# custom_hat_v_beta.net
KiCad netlist of a schematic drawn in EAGLE
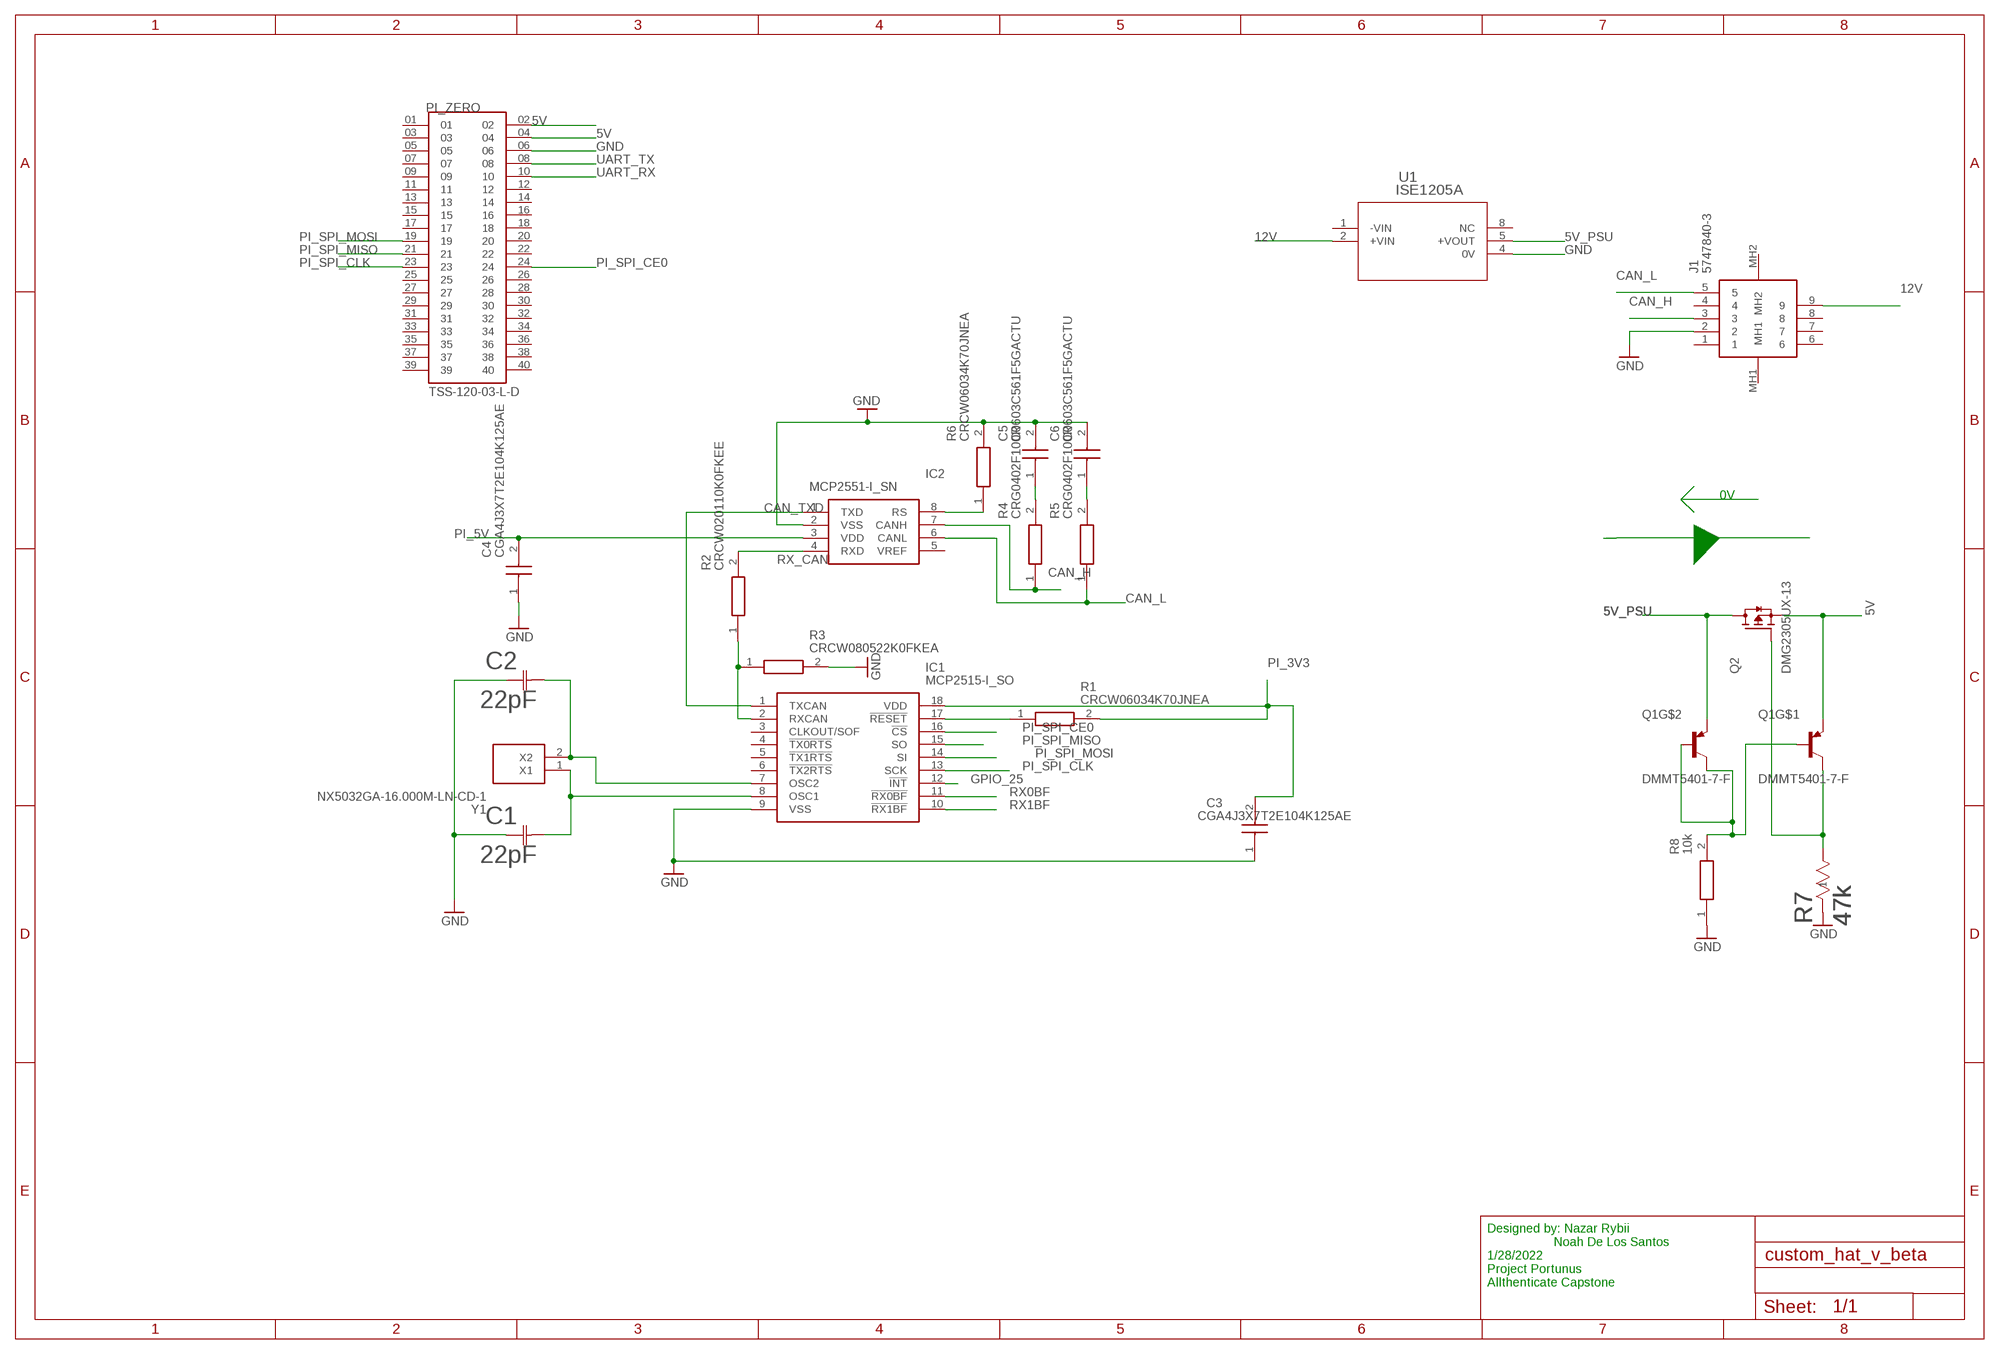
[diagram p0: schematic, sheet 1]

(export (version "E")
  (design (tool "Eeschema 10.0.6"))
  (components
    (comp (ref "C1")
      (value "22pF")
      (footprint "eagle-import:CAP_CL21_SAM")
      (fields
        (field (name "MANUFACTURER_PART_NUMBER") "CL21C220JBANNNC")
        (field (name "COPYRIGHT") "Copyright (C) 2022 Ultra Librarian. All rights reserved.")
      )
      (libsource (lib "eagle-import") (part "CL21C220JBANNNC"))
    )
    (comp (ref "C2")
      (value "22pF")
      (footprint "eagle-import:CAP_CL21_SAM")
      (fields
        (field (name "MANUFACTURER_PART_NUMBER") "CL21C220JBANNNC")
        (field (name "COPYRIGHT") "Copyright (C) 2022 Ultra Librarian. All rights reserved.")
      )
      (libsource (lib "eagle-import") (part "CL21C220JBANNNC"))
    )
    (comp (ref "C3")
      (value "CGA4J3X7T2E104K125AE")
      (footprint "eagle-import:CAPC2012X145N")
      (fields (field (name "MOUSER_PART_NUMBER") "810-CGA4J3X7T2E104KS"))
      (libsource (lib "eagle-import") (part "CGA4J3X7T2E104K125AE"))
    )
    (comp (ref "C4")
      (value "CGA4J3X7T2E104K125AE")
      (footprint "eagle-import:CAPC2012X145N")
      (fields (field (name "MOUSER_PART_NUMBER") "810-CGA4J3X7T2E104KS"))
      (libsource (lib "eagle-import") (part "CGA4J3X7T2E104K125AE"))
    )
    (comp (ref "C5")
      (value "C0603C561F5GACTU")
      (footprint "eagle-import:CAPC1608X87N")
      (fields (field (name "MOUSER_PART_NUMBER") "80-C0603C561F5G"))
      (libsource (lib "eagle-import") (part "C0603C561F5GACTU"))
    )
    (comp (ref "C6")
      (value "C0603C561F5GACTU")
      (footprint "eagle-import:CAPC1608X87N")
      (fields (field (name "MOUSER_PART_NUMBER") "80-C0603C561F5G"))
      (libsource (lib "eagle-import") (part "C0603C561F5GACTU"))
    )
    (comp (ref "IC1")
      (value "MCP2515-I_SO")
      (footprint "eagle-import:SOIC127P1030X265-18N")
      (fields
        (field (name "ARROW_PART_NUMBER") "MCP2515-I/SO")
        (field (name "MOUSER_PART_NUMBER") "579-MCP2515-I/SO")
      )
      (libsource (lib "eagle-import") (part "MCP2515-I_SO"))
    )
    (comp (ref "IC2")
      (value "MCP2551-I_SN")
      (footprint "eagle-import:SOIC127P600X175-8N")
      (fields
        (field (name "ARROW_PART_NUMBER") "MCP2551-I/SN")
        (field (name "MOUSER_PART_NUMBER") "579-MCP2551-I/SN")
      )
      (libsource (lib "eagle-import") (part "MCP2551-I_SN"))
    )
    (comp (ref "J1")
      (value "5747840-3")
      (footprint "eagle-import:57478403")
      (fields (field (name "MOUSER_PART_NUMBER") "571-5747840-3"))
      (libsource (lib "eagle-import") (part "5747840-3"))
    )
    (comp (ref "PI_ZERO")
      (value "TSS-120-03-L-D")
      (footprint "eagle-import:SAMTEC_TSS-120-03-L-D")
      (fields (field (name "MF") "Samtec"))
      (libsource (lib "eagle-import") (part "TSS-120-03-L-D"))
    )
    (comp (ref "Q1")
      (value "DMMT5401-7-F")
      (footprint "eagle-import:SOT95P285X140-6N")
      (fields (field (name "MF") "Diodes Inc."))
      (libsource (lib "eagle-import") (part "DMMT5401-7-F"))
    )
    (comp (ref "Q2")
      (value "DMG2305UX-13")
      (footprint "eagle-import:SOT91P240X110-3N")
      (fields (field (name "MF") "Diodes Inc."))
      (libsource (lib "eagle-import") (part "DMG2305UX-13"))
    )
    (comp (ref "R1")
      (value "CRCW06034K70JNEA")
      (footprint "eagle-import:RESC1608X50N")
      (fields (field (name "MOUSER_PART_NUMBER") "71-CRCW0603J-4.7K-E3"))
      (libsource (lib "eagle-import") (part "CRCW06034K70JNEA"))
    )
    (comp (ref "R2")
      (value "CRCW020110K0FKEE")
      (footprint "eagle-import:RESC0603X28N")
      (libsource (lib "eagle-import") (part "CRCW020110K0FKEE"))
    )
    (comp (ref "R3")
      (value "CRCW080522K0FKEA")
      (footprint "eagle-import:RESC2012X50N")
      (fields (field (name "MOUSER_PART_NUMBER") "71-CRCW0805-22K-E3"))
      (libsource (lib "eagle-import") (part "CRCW080522K0FKEA"))
    )
    (comp (ref "R4")
      (value "CRG0402F100R")
      (footprint "eagle-import:RESC1005X40N")
      (fields (field (name "MOUSER_PART_NUMBER") "279-CRG0402F100R"))
      (libsource (lib "eagle-import") (part "CRG0402F100R"))
    )
    (comp (ref "R5")
      (value "CRG0402F100R")
      (footprint "eagle-import:RESC1005X40N")
      (fields (field (name "MOUSER_PART_NUMBER") "279-CRG0402F100R"))
      (libsource (lib "eagle-import") (part "CRG0402F100R"))
    )
    (comp (ref "R6")
      (value "CRCW06034K70JNEA")
      (footprint "eagle-import:RESC1608X50N")
      (fields (field (name "MOUSER_PART_NUMBER") "71-CRCW0603J-4.7K-E3"))
      (libsource (lib "eagle-import") (part "CRCW06034K70JNEA"))
    )
    (comp (ref "R7")
      (value "47k")
      (footprint "eagle-import:RC0603N_YAG")
      (fields
        (field (name "MANUFACTURER_PART_NUMBER") "RC0603FR-0747KL")
        (field (name "COPYRIGHT") "Copyright (C) 2022 Ultra Librarian. All rights reserved.")
      )
      (libsource (lib "eagle-import") (part "RC0603FR-0747KL"))
    )
    (comp (ref "R8")
      (value "10k")
      (footprint "eagle-import:RESC2012X50N")
      (fields
        (field (name "ARROW_PART_NUMBER") "CRCW080510K0FKEC")
        (field (name "MOUSER_PART_NUMBER") "71-CRCW080510K0FKEC")
      )
      (libsource (lib "eagle-import") (part "CRCW080510K0FKEC"))
    )
    (comp (ref "U1")
      (value "ISE1205A")
      (footprint "eagle-import:ISE1205A_XPP")
      (fields (field (name "COPYRIGHT") "Copyright (C) 2022 Ultra Librarian. All rights reserved."))
      (libsource (lib "eagle-import") (part "ISE1205A"))
    )
    (comp (ref "Y1")
      (value "NX5032GA-16.000M-LN-CD-1")
      (footprint "eagle-import:NX5032GA16000000MHZLNCD1")
      (fields (field (name "MOUSER_PART_NUMBER") "344-NX5032GA16MLNCD1"))
      (libsource (lib "eagle-import") (part "NX5032GA-16.000M-LN-CD-1"))
    )
  )
  (nets
    (net (code "1") (name "/-VIN") (class "Default")
      (node (ref "U1") (pin "1") (pinfunction "-VIN_1") (pintype "power_in"))
    )
    (net (code "2") (name "/5V") (class "Default")
      (node (ref "PI_ZERO") (pin "02") (pinfunction "02_02") (pintype "passive"))
      (node (ref "PI_ZERO") (pin "04") (pinfunction "04_04") (pintype "passive"))
      (node (ref "Q1") (pin "6") (pinfunction "E_6") (pintype "passive"))
      (node (ref "Q2") (pin "2") (pinfunction "S_2") (pintype "passive"))
    )
    (net (code "3") (name "/5V_PSU") (class "Default")
      (node (ref "Q1") (pin "5") (pinfunction "E_5") (pintype "passive"))
      (node (ref "Q2") (pin "3") (pinfunction "D_3") (pintype "passive"))
      (node (ref "U1") (pin "5") (pinfunction "+VOUT_5") (pintype "output"))
    )
    (net (code "4") (name "/12V") (class "Default")
      (node (ref "J1") (pin "9") (pinfunction "9_9") (pintype "bidirectional"))
      (node (ref "U1") (pin "2") (pinfunction "+VIN_2") (pintype "power_in"))
    )
    (net (code "5") (name "/CAN_H") (class "Default")
      (node (ref "IC2") (pin "7") (pinfunction "CANH_7") (pintype "bidirectional"))
      (node (ref "J1") (pin "3") (pinfunction "3_3") (pintype "bidirectional"))
      (node (ref "R4") (pin "1") (pinfunction "1_1") (pintype "bidirectional"))
    )
    (net (code "6") (name "/CAN_L") (class "Default")
      (node (ref "IC2") (pin "6") (pinfunction "CANL_6") (pintype "bidirectional"))
      (node (ref "J1") (pin "5") (pinfunction "5_5") (pintype "bidirectional"))
      (node (ref "R5") (pin "1") (pinfunction "1_1") (pintype "bidirectional"))
    )
    (net (code "7") (name "/CAN_TXD") (class "Default")
      (node (ref "IC1") (pin "1") (pinfunction "TXCAN_1") (pintype "bidirectional"))
      (node (ref "IC2") (pin "1") (pinfunction "TXD_1") (pintype "bidirectional"))
    )
    (net (code "8") (name "/GPIO_25") (class "Default")
      (node (ref "IC1") (pin "12") (pinfunction "~{INT}_12") (pintype "bidirectional"))
    )
    (net (code "9") (name "/PI_3V3") (class "Default")
      (node (ref "C3") (pin "2") (pinfunction "2_2") (pintype "bidirectional"))
      (node (ref "IC1") (pin "18") (pinfunction "VDD_18") (pintype "bidirectional"))
      (node (ref "R1") (pin "2") (pinfunction "2_2") (pintype "bidirectional"))
    )
    (net (code "10") (name "/PI_5V") (class "Default")
      (node (ref "C4") (pin "2") (pinfunction "2_2") (pintype "bidirectional"))
      (node (ref "IC2") (pin "3") (pinfunction "VDD_3") (pintype "bidirectional"))
    )
    (net (code "11") (name "/PI_SPI_CE0") (class "Default")
      (node (ref "IC1") (pin "16") (pinfunction "~{CS}_16") (pintype "bidirectional"))
      (node (ref "PI_ZERO") (pin "24") (pinfunction "24_24") (pintype "passive"))
    )
    (net (code "12") (name "/PI_SPI_CLK") (class "Default")
      (node (ref "IC1") (pin "13") (pinfunction "SCK_13") (pintype "bidirectional"))
      (node (ref "PI_ZERO") (pin "23") (pinfunction "23_23") (pintype "passive"))
    )
    (net (code "13") (name "/PI_SPI_MISO") (class "Default")
      (node (ref "IC1") (pin "15") (pinfunction "SO_15") (pintype "bidirectional"))
      (node (ref "PI_ZERO") (pin "21") (pinfunction "21_21") (pintype "passive"))
    )
    (net (code "14") (name "/PI_SPI_MOSI") (class "Default")
      (node (ref "IC1") (pin "14") (pinfunction "SI_14") (pintype "bidirectional"))
      (node (ref "PI_ZERO") (pin "19") (pinfunction "19_19") (pintype "passive"))
    )
    (net (code "15") (name "/RX0BF") (class "Default")
      (node (ref "IC1") (pin "11") (pinfunction "~{RX0BF}_11") (pintype "bidirectional"))
    )
    (net (code "16") (name "/RX1BF") (class "Default")
      (node (ref "IC1") (pin "10") (pinfunction "~{RX1BF}_10") (pintype "bidirectional"))
    )
    (net (code "17") (name "/RX_CAN") (class "Default")
      (node (ref "IC2") (pin "4") (pinfunction "RXD_4") (pintype "bidirectional"))
      (node (ref "R2") (pin "2") (pinfunction "2_2") (pintype "bidirectional"))
    )
    (net (code "18") (name "/UART_RX") (class "Default")
      (node (ref "PI_ZERO") (pin "10") (pinfunction "10_10") (pintype "passive"))
    )
    (net (code "19") (name "/UART_TX") (class "Default")
      (node (ref "PI_ZERO") (pin "08") (pinfunction "08_08") (pintype "passive"))
    )
    (net (code "20") (name "GND") (class "Default")
      (node (ref "C1") (pin "1") (pinfunction "1_1") (pintype "passive"))
      (node (ref "C2") (pin "1") (pinfunction "1_1") (pintype "passive"))
      (node (ref "C3") (pin "1") (pinfunction "1_1") (pintype "bidirectional"))
      (node (ref "C4") (pin "1") (pinfunction "1_1") (pintype "bidirectional"))
      (node (ref "C5") (pin "2") (pinfunction "2_2") (pintype "bidirectional"))
      (node (ref "C6") (pin "2") (pinfunction "2_2") (pintype "bidirectional"))
      (node (ref "IC1") (pin "9") (pinfunction "VSS_9") (pintype "bidirectional"))
      (node (ref "IC2") (pin "2") (pinfunction "VSS_2") (pintype "bidirectional"))
      (node (ref "J1") (pin "2") (pinfunction "2_2") (pintype "bidirectional"))
      (node (ref "PI_ZERO") (pin "06") (pinfunction "06_06") (pintype "passive"))
      (node (ref "R3") (pin "2") (pinfunction "2_2") (pintype "bidirectional"))
      (node (ref "R6") (pin "2") (pinfunction "2_2") (pintype "bidirectional"))
      (node (ref "R7") (pin "1") (pinfunction "1_1") (pintype "passive"))
      (node (ref "R8") (pin "1") (pinfunction "1_1") (pintype "bidirectional"))
      (node (ref "U1") (pin "4") (pinfunction "0V_4") (pintype "bidirectional"))
    )
    (net (code "21") (name "Net-(C5-Pad1)") (class "Default")
      (node (ref "C5") (pin "1") (pinfunction "1_1") (pintype "bidirectional"))
      (node (ref "R4") (pin "2") (pinfunction "2_2") (pintype "bidirectional"))
    )
    (net (code "22") (name "Net-(C6-Pad1)") (class "Default")
      (node (ref "C6") (pin "1") (pinfunction "1_1") (pintype "bidirectional"))
      (node (ref "R5") (pin "2") (pinfunction "2_2") (pintype "bidirectional"))
    )
    (net (code "23") (name "Net-(IC1-OSC1)") (class "Default")
      (node (ref "C1") (pin "2") (pinfunction "2_2") (pintype "passive"))
      (node (ref "IC1") (pin "8") (pinfunction "OSC1_8") (pintype "bidirectional"))
      (node (ref "Y1") (pin "1") (pinfunction "X1_1") (pintype "bidirectional"))
    )
    (net (code "24") (name "Net-(IC1-OSC2)") (class "Default")
      (node (ref "C2") (pin "2") (pinfunction "2_2") (pintype "passive"))
      (node (ref "IC1") (pin "7") (pinfunction "OSC2_7") (pintype "bidirectional"))
      (node (ref "Y1") (pin "2") (pinfunction "X2_2") (pintype "bidirectional"))
    )
    (net (code "25") (name "Net-(IC1-RXCAN)") (class "Default")
      (node (ref "IC1") (pin "2") (pinfunction "RXCAN_2") (pintype "bidirectional"))
      (node (ref "R2") (pin "1") (pinfunction "1_1") (pintype "bidirectional"))
      (node (ref "R3") (pin "1") (pinfunction "1_1") (pintype "bidirectional"))
    )
    (net (code "26") (name "Net-(IC1-~{RESET})") (class "Default")
      (node (ref "IC1") (pin "17") (pinfunction "~{RESET}_17") (pintype "bidirectional"))
      (node (ref "R1") (pin "1") (pinfunction "1_1") (pintype "bidirectional"))
    )
    (net (code "27") (name "Net-(IC2-RS)") (class "Default")
      (node (ref "IC2") (pin "8") (pinfunction "RS_8") (pintype "bidirectional"))
      (node (ref "R6") (pin "1") (pinfunction "1_1") (pintype "bidirectional"))
    )
    (net (code "28") (name "Net-(Q1A-B)") (class "Default")
      (node (ref "Q1") (pin "2") (pinfunction "B_2") (pintype "passive"))
      (node (ref "Q1") (pin "3") (pinfunction "B_3") (pintype "passive"))
      (node (ref "Q1") (pin "4") (pinfunction "C_4") (pintype "passive"))
      (node (ref "R8") (pin "2") (pinfunction "2_2") (pintype "bidirectional"))
    )
    (net (code "29") (name "Net-(Q1A-C)") (class "Default")
      (node (ref "Q1") (pin "1") (pinfunction "C_1") (pintype "passive"))
      (node (ref "Q2") (pin "1") (pinfunction "G_1") (pintype "passive"))
      (node (ref "R7") (pin "2") (pinfunction "2_2") (pintype "passive"))
    )
    (net (code "30") (name "unconnected-(IC1-CLKOUT{slash}SOF-Pad3)") (class "Default")
      (node (ref "IC1") (pin "3") (pinfunction "CLKOUT/SOF_3") (pintype "bidirectional"))
    )
    (net (code "31") (name "unconnected-(IC1-~{TX0RTS}-Pad4)") (class "Default")
      (node (ref "IC1") (pin "4") (pinfunction "~{TX0RTS}_4") (pintype "bidirectional"))
    )
    (net (code "32") (name "unconnected-(IC1-~{TX1RTS}-Pad5)") (class "Default")
      (node (ref "IC1") (pin "5") (pinfunction "~{TX1RTS}_5") (pintype "bidirectional"))
    )
    (net (code "33") (name "unconnected-(IC1-~{TX2RTS}-Pad6)") (class "Default")
      (node (ref "IC1") (pin "6") (pinfunction "~{TX2RTS}_6") (pintype "bidirectional"))
    )
    (net (code "34") (name "unconnected-(IC2-VREF-Pad5)") (class "Default")
      (node (ref "IC2") (pin "5") (pinfunction "VREF_5") (pintype "bidirectional"))
    )
    (net (code "35") (name "unconnected-(J1-Pad1)") (class "Default")
      (node (ref "J1") (pin "1") (pinfunction "1_1") (pintype "bidirectional"))
    )
    (net (code "36") (name "unconnected-(J1-Pad4)") (class "Default")
      (node (ref "J1") (pin "4") (pinfunction "4_4") (pintype "bidirectional"))
    )
    (net (code "37") (name "unconnected-(J1-Pad6)") (class "Default")
      (node (ref "J1") (pin "6") (pinfunction "6_6") (pintype "bidirectional"))
    )
    (net (code "38") (name "unconnected-(J1-Pad7)") (class "Default")
      (node (ref "J1") (pin "7") (pinfunction "7_7") (pintype "bidirectional"))
    )
    (net (code "39") (name "unconnected-(J1-Pad8)") (class "Default")
      (node (ref "J1") (pin "8") (pinfunction "8_8") (pintype "bidirectional"))
    )
    (net (code "40") (name "unconnected-(J1-PadMH1)") (class "Default")
      (node (ref "J1") (pin "MH1") (pinfunction "MH1_MH1") (pintype "bidirectional"))
    )
    (net (code "41") (name "unconnected-(J1-PadMH2)") (class "Default")
      (node (ref "J1") (pin "MH2") (pinfunction "MH2_MH2") (pintype "bidirectional"))
    )
    (net (code "42") (name "unconnected-(PI_ZERO-Pad01)") (class "Default")
      (node (ref "PI_ZERO") (pin "01") (pinfunction "01_01") (pintype "passive"))
    )
    (net (code "43") (name "unconnected-(PI_ZERO-Pad03)") (class "Default")
      (node (ref "PI_ZERO") (pin "03") (pinfunction "03_03") (pintype "passive"))
    )
    (net (code "44") (name "unconnected-(PI_ZERO-Pad05)") (class "Default")
      (node (ref "PI_ZERO") (pin "05") (pinfunction "05_05") (pintype "passive"))
    )
    (net (code "45") (name "unconnected-(PI_ZERO-Pad07)") (class "Default")
      (node (ref "PI_ZERO") (pin "07") (pinfunction "07_07") (pintype "passive"))
    )
    (net (code "46") (name "unconnected-(PI_ZERO-Pad09)") (class "Default")
      (node (ref "PI_ZERO") (pin "09") (pinfunction "09_09") (pintype "passive"))
    )
    (net (code "47") (name "unconnected-(PI_ZERO-Pad11)") (class "Default")
      (node (ref "PI_ZERO") (pin "11") (pinfunction "11_11") (pintype "passive"))
    )
    (net (code "48") (name "unconnected-(PI_ZERO-Pad12)") (class "Default")
      (node (ref "PI_ZERO") (pin "12") (pinfunction "12_12") (pintype "passive"))
    )
    (net (code "49") (name "unconnected-(PI_ZERO-Pad13)") (class "Default")
      (node (ref "PI_ZERO") (pin "13") (pinfunction "13_13") (pintype "passive"))
    )
    (net (code "50") (name "unconnected-(PI_ZERO-Pad14)") (class "Default")
      (node (ref "PI_ZERO") (pin "14") (pinfunction "14_14") (pintype "passive"))
    )
    (net (code "51") (name "unconnected-(PI_ZERO-Pad15)") (class "Default")
      (node (ref "PI_ZERO") (pin "15") (pinfunction "15_15") (pintype "passive"))
    )
    (net (code "52") (name "unconnected-(PI_ZERO-Pad16)") (class "Default")
      (node (ref "PI_ZERO") (pin "16") (pinfunction "16_16") (pintype "passive"))
    )
    (net (code "53") (name "unconnected-(PI_ZERO-Pad17)") (class "Default")
      (node (ref "PI_ZERO") (pin "17") (pinfunction "17_17") (pintype "passive"))
    )
    (net (code "54") (name "unconnected-(PI_ZERO-Pad18)") (class "Default")
      (node (ref "PI_ZERO") (pin "18") (pinfunction "18_18") (pintype "passive"))
    )
    (net (code "55") (name "unconnected-(PI_ZERO-Pad20)") (class "Default")
      (node (ref "PI_ZERO") (pin "20") (pinfunction "20_20") (pintype "passive"))
    )
    (net (code "56") (name "unconnected-(PI_ZERO-Pad22)") (class "Default")
      (node (ref "PI_ZERO") (pin "22") (pinfunction "22_22") (pintype "passive"))
    )
    (net (code "57") (name "unconnected-(PI_ZERO-Pad25)") (class "Default")
      (node (ref "PI_ZERO") (pin "25") (pinfunction "25_25") (pintype "passive"))
    )
    (net (code "58") (name "unconnected-(PI_ZERO-Pad26)") (class "Default")
      (node (ref "PI_ZERO") (pin "26") (pinfunction "26_26") (pintype "passive"))
    )
    (net (code "59") (name "unconnected-(PI_ZERO-Pad27)") (class "Default")
      (node (ref "PI_ZERO") (pin "27") (pinfunction "27_27") (pintype "passive"))
    )
    (net (code "60") (name "unconnected-(PI_ZERO-Pad28)") (class "Default")
      (node (ref "PI_ZERO") (pin "28") (pinfunction "28_28") (pintype "passive"))
    )
    (net (code "61") (name "unconnected-(PI_ZERO-Pad29)") (class "Default")
      (node (ref "PI_ZERO") (pin "29") (pinfunction "29_29") (pintype "passive"))
    )
    (net (code "62") (name "unconnected-(PI_ZERO-Pad30)") (class "Default")
      (node (ref "PI_ZERO") (pin "30") (pinfunction "30_30") (pintype "passive"))
    )
    (net (code "63") (name "unconnected-(PI_ZERO-Pad31)") (class "Default")
      (node (ref "PI_ZERO") (pin "31") (pinfunction "31_31") (pintype "passive"))
    )
    (net (code "64") (name "unconnected-(PI_ZERO-Pad32)") (class "Default")
      (node (ref "PI_ZERO") (pin "32") (pinfunction "32_32") (pintype "passive"))
    )
    (net (code "65") (name "unconnected-(PI_ZERO-Pad33)") (class "Default")
      (node (ref "PI_ZERO") (pin "33") (pinfunction "33_33") (pintype "passive"))
    )
    (net (code "66") (name "unconnected-(PI_ZERO-Pad34)") (class "Default")
      (node (ref "PI_ZERO") (pin "34") (pinfunction "34_34") (pintype "passive"))
    )
    (net (code "67") (name "unconnected-(PI_ZERO-Pad35)") (class "Default")
      (node (ref "PI_ZERO") (pin "35") (pinfunction "35_35") (pintype "passive"))
    )
    (net (code "68") (name "unconnected-(PI_ZERO-Pad36)") (class "Default")
      (node (ref "PI_ZERO") (pin "36") (pinfunction "36_36") (pintype "passive"))
    )
    (net (code "69") (name "unconnected-(PI_ZERO-Pad37)") (class "Default")
      (node (ref "PI_ZERO") (pin "37") (pinfunction "37_37") (pintype "passive"))
    )
    (net (code "70") (name "unconnected-(PI_ZERO-Pad38)") (class "Default")
      (node (ref "PI_ZERO") (pin "38") (pinfunction "38_38") (pintype "passive"))
    )
    (net (code "71") (name "unconnected-(PI_ZERO-Pad39)") (class "Default")
      (node (ref "PI_ZERO") (pin "39") (pinfunction "39_39") (pintype "passive"))
    )
    (net (code "72") (name "unconnected-(PI_ZERO-Pad40)") (class "Default")
      (node (ref "PI_ZERO") (pin "40") (pinfunction "40_40") (pintype "passive"))
    )
    (net (code "73") (name "unconnected-(U1-NC-Pad8)") (class "Default")
      (node (ref "U1") (pin "8") (pinfunction "NC_8") (pintype "no_connect"))
    )
  )
)
